# Main.net
KiCad netlist of a schematic drawn in Altium Designer
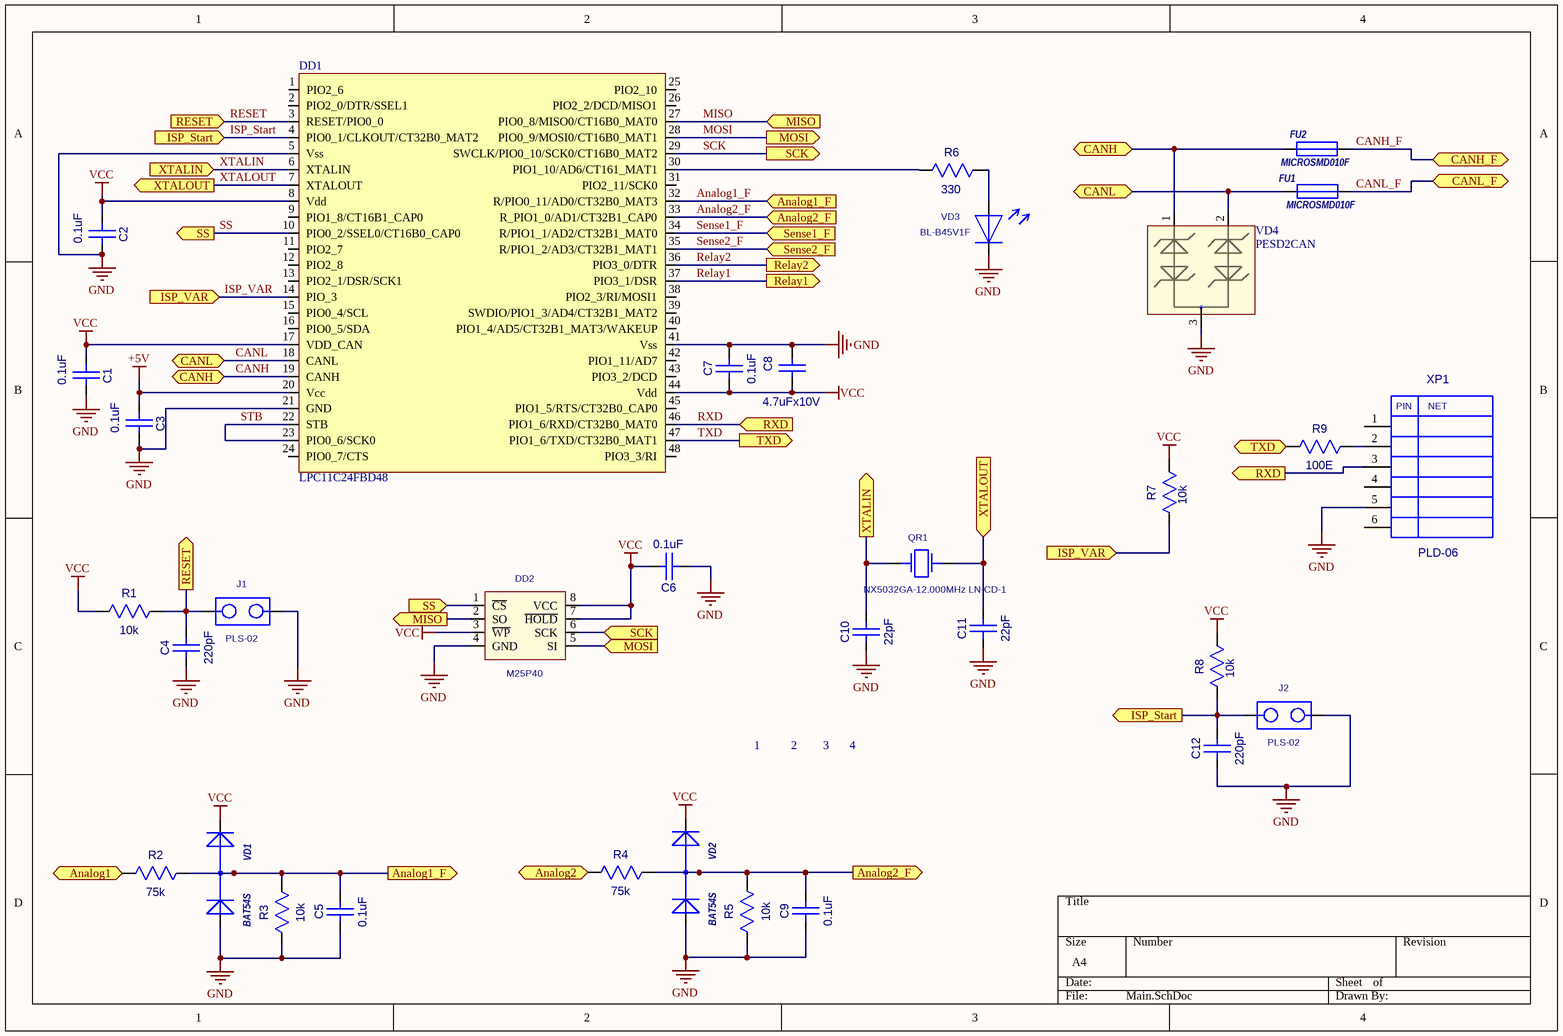
[diagram p0: Main.SchDoc]

(export (version "E")
  (design (tool "Eeschema 10.0.6"))
  (components
    (comp (ref "1")
      (value "REPER1.2")
      (footprint "REPER1.2")
      (libsource (lib "gprs_modem") (part "REPER1.2"))
    )
    (comp (ref "2")
      (value "REPER1.2")
      (footprint "REPER1.2")
      (libsource (lib "gprs_modem") (part "REPER1.2"))
    )
    (comp (ref "3")
      (value "REPER1.2")
      (footprint "REPER1.2")
      (libsource (lib "gprs_modem") (part "REPER1.2"))
    )
    (comp (ref "4")
      (value "REPER1.2")
      (footprint "REPER1.2")
      (libsource (lib "gprs_modem") (part "REPER1.2"))
    )
    (comp (ref "C1")
      (value "0.1uF")
      (footprint "CC0603-3M")
      (description "CC0603")
      (libsource (lib "gprs_modem") (part "CC0603"))
    )
    (comp (ref "C2")
      (value "0.1uF")
      (footprint "CC0603-3M")
      (description "CC0603")
      (libsource (lib "gprs_modem") (part "CC0603"))
    )
    (comp (ref "C3")
      (value "0.1uF")
      (footprint "CC0603-3M")
      (description "CC0603")
      (libsource (lib "gprs_modem") (part "CC0603"))
    )
    (comp (ref "C4")
      (value "220pF")
      (footprint "CC0603-3M")
      (description "CC0603")
      (libsource (lib "gprs_modem") (part "CC0603"))
    )
    (comp (ref "C5")
      (value "0.1uF")
      (footprint "CC0603-3M")
      (description "CC0603")
      (libsource (lib "gprs_modem") (part "CC0603"))
    )
    (comp (ref "C6")
      (value "0.1uF")
      (footprint "CC0603-3M")
      (description "CC0603")
      (libsource (lib "gprs_modem") (part "CC0603"))
    )
    (comp (ref "C7")
      (value "0.1uF")
      (footprint "CC0603-3M")
      (description "CC0603")
      (libsource (lib "gprs_modem") (part "CC0603"))
    )
    (comp (ref "C8")
      (value "4.7uFx10V")
      (footprint "CC0805-MIDI-2M1")
      (description "CC0805")
      (libsource (lib "gprs_modem") (part "CC0805"))
    )
    (comp (ref "C9")
      (value "0.1uF")
      (footprint "CC0603-3M")
      (description "CC0603")
      (libsource (lib "gprs_modem") (part "CC0603"))
    )
    (comp (ref "C10")
      (value "22pF")
      (footprint "CC0603-3M")
      (description "CC0603")
      (libsource (lib "gprs_modem") (part "CC0603"))
    )
    (comp (ref "C11")
      (value "22pF")
      (footprint "CC0603-3M")
      (description "CC0603")
      (libsource (lib "gprs_modem") (part "CC0603"))
    )
    (comp (ref "C12")
      (value "220pF")
      (footprint "CC0603-3M")
      (description "CC0603")
      (libsource (lib "gprs_modem") (part "CC0603"))
    )
    (comp (ref "DD1")
      (value "LPC11C24FBD48")
      (footprint "LQFP-48")
      (libsource (lib "gprs_modem_2") (part "LPC11C24FBD48"))
    )
    (comp (ref "DD2")
      (value "M25P40")
      (footprint "EIAJ_SO8")
      (description "S25FL016A0LMFI01")
      (libsource (lib "gprs_modem") (part "S25FL016A0LMFI01"))
    )
    (comp (ref "FU1")
      (value "MICROSMD010F")
      (footprint "RC1210")
      (description "MICROSMD")
      (libsource (lib "Schetchik") (part "MICROSMD"))
    )
    (comp (ref "FU2")
      (value "MICROSMD010F")
      (footprint "RC1210")
      (description "MICROSMD")
      (libsource (lib "Schetchik") (part "MICROSMD"))
    )
    (comp (ref "J1") (value "PLS-02") (footprint "PLS-02") (libsource (lib "gprs_modem") (part "PLS-02")))
    (comp (ref "J2") (value "PLS-02") (footprint "PLS-02") (libsource (lib "gprs_modem") (part "PLS-02")))
    (comp (ref "QR1")
      (value "NX5032GA-12.000MHz LN-CD-1")
      (footprint "AC5032_2")
      (description "AC5032/2")
      (libsource (lib "gprs_modem") (part "AC5032_2"))
    )
    (comp (ref "R1")
      (value "10k")
      (footprint "RC0603-3M")
      (description "RC0603")
      (libsource (lib "gprs_modem") (part "RC0603"))
    )
    (comp (ref "R2")
      (value "75k")
      (footprint "RC0603-3M")
      (description "RC0603")
      (libsource (lib "gprs_modem") (part "RC0603"))
    )
    (comp (ref "R3")
      (value "10k")
      (footprint "RC0603-3M")
      (description "RC0603")
      (libsource (lib "gprs_modem") (part "RC0603"))
    )
    (comp (ref "R4")
      (value "75k")
      (footprint "RC0603-3M")
      (description "RC0603")
      (libsource (lib "gprs_modem") (part "RC0603"))
    )
    (comp (ref "R5")
      (value "10k")
      (footprint "RC0603-3M")
      (description "RC0603")
      (libsource (lib "gprs_modem") (part "RC0603"))
    )
    (comp (ref "R6")
      (value "330")
      (footprint "RC0603-3M")
      (description "RC0603")
      (libsource (lib "gprs_modem") (part "RC0603"))
    )
    (comp (ref "R7")
      (value "10k")
      (footprint "RC0603-3M")
      (description "RC0603")
      (libsource (lib "gprs_modem") (part "RC0603"))
    )
    (comp (ref "R8")
      (value "10k")
      (footprint "RC0603-3M")
      (description "RC0603")
      (libsource (lib "gprs_modem") (part "RC0603"))
    )
    (comp (ref "R9")
      (value "100E")
      (footprint "RC0603-3M")
      (description "RC0603")
      (libsource (lib "gprs_modem") (part "RC0603"))
    )
    (comp (ref "VD1")
      (value "BAT54S")
      (footprint "SOT-23(GSD)")
      (description "1.0 Ampere General Purpose Rectifier")
      (libsource (lib "gprs_modem") (part "BAT54S"))
    )
    (comp (ref "VD2")
      (value "BAT54S")
      (footprint "SOT-23(GSD)")
      (description "1.0 Ampere General Purpose Rectifier")
      (libsource (lib "gprs_modem") (part "BAT54S"))
    )
    (comp (ref "VD3")
      (value "BL-B45V1F")
      (footprint "LED3")
      (description "LED_3")
      (libsource (lib "gprs_modem") (part "LED_3"))
    )
    (comp (ref "VD4")
      (value "PESD2CAN")
      (footprint "SOT-23(123)")
      (description "TVS for CAN")
      (libsource (lib "gprs_modem") (part "PESD2CAN"))
    )
    (comp (ref "XP1")
      (value "PLD-06")
      (footprint "PIN6")
      (description "PLD06")
      (libsource (lib "gprs_modem") (part "PLD-06"))
    )
  )
  (nets
    (net (code "1") (name "+5V") (class "Default")
      (node (ref "C3") (pin "1") (pinfunction "A_1") (pintype "passive"))
      (node (ref "DD1") (pin "20") (pinfunction "Vcc_20") (pintype "passive"))
    )
    (net (code "2") (name "/Analog1") (class "Default")
      (node (ref "R2") (pin "1") (pinfunction "A_1") (pintype "passive"))
    )
    (net (code "3") (name "/Analog1_F") (class "Default")
      (node (ref "C5") (pin "2") (pinfunction "B_2") (pintype "passive"))
      (node (ref "DD1") (pin "32") (pinfunction "R/PIO0_11/AD0/CT32B0_MAT3_32") (pintype "passive"))
      (node (ref "R2") (pin "2") (pinfunction "B_2") (pintype "passive"))
      (node (ref "R3") (pin "2") (pinfunction "B_2") (pintype "passive"))
      (node (ref "VD1") (pin "3") (pinfunction "AK_3") (pintype "passive"))
    )
    (net (code "4") (name "/Analog2") (class "Default")
      (node (ref "R4") (pin "1") (pinfunction "A_1") (pintype "passive"))
    )
    (net (code "5") (name "/Analog2_F") (class "Default")
      (node (ref "C9") (pin "2") (pinfunction "B_2") (pintype "passive"))
      (node (ref "DD1") (pin "33") (pinfunction "R_PIO1_0/AD1/CT32B1_CAP0_33") (pintype "passive"))
      (node (ref "R4") (pin "2") (pinfunction "B_2") (pintype "passive"))
      (node (ref "R5") (pin "2") (pinfunction "B_2") (pintype "passive"))
      (node (ref "VD2") (pin "3") (pinfunction "AK_3") (pintype "passive"))
    )
    (net (code "6") (name "/CANH") (class "Default")
      (node (ref "DD1") (pin "19") (pinfunction "CANH_19") (pintype "passive"))
      (node (ref "FU2") (pin "1") (pintype "passive"))
      (node (ref "VD4") (pin "1") (pinfunction "1_1") (pintype "passive"))
    )
    (net (code "7") (name "/CANH_F") (class "Default") (node (ref "FU2") (pin "2") (pintype "passive")))
    (net (code "8") (name "/CANL") (class "Default")
      (node (ref "DD1") (pin "18") (pinfunction "CANL_18") (pintype "passive"))
      (node (ref "FU1") (pin "1") (pintype "passive"))
      (node (ref "VD4") (pin "2") (pinfunction "2_2") (pintype "passive"))
    )
    (net (code "9") (name "/CANL_F") (class "Default") (node (ref "FU1") (pin "2") (pintype "passive")))
    (net (code "10") (name "/ISP_Start") (class "Default")
      (node (ref "C12") (pin "2") (pinfunction "B_2") (pintype "passive"))
      (node (ref "DD1") (pin "4") (pinfunction "PIO0_1/CLKOUT/CT32B0_MAT2_4") (pintype "passive"))
      (node (ref "J2") (pin "1") (pintype "passive"))
      (node (ref "R8") (pin "1") (pinfunction "A_1") (pintype "passive"))
    )
    (net (code "11") (name "/ISP_VAR") (class "Default")
      (node (ref "DD1") (pin "14") (pinfunction "PIO_3_14") (pintype "passive"))
      (node (ref "R7") (pin "1") (pinfunction "A_1") (pintype "passive"))
    )
    (net (code "12") (name "/MISO") (class "Default")
      (node (ref "DD1") (pin "27") (pinfunction "PIO0_8/MISO0/CT16B0_MAT0_27") (pintype "passive"))
      (node (ref "DD2") (pin "2") (pinfunction "SO_2") (pintype "passive"))
    )
    (net (code "13") (name "/MOSI") (class "Default")
      (node (ref "DD1") (pin "28") (pinfunction "PIO0_9/MOSI0/CT16B0_MAT1_28") (pintype "passive"))
      (node (ref "DD2") (pin "5") (pinfunction "SI_5") (pintype "passive"))
    )
    (net (code "14") (name "/RESET") (class "Default")
      (node (ref "C4") (pin "2") (pinfunction "B_2") (pintype "passive"))
      (node (ref "DD1") (pin "3") (pinfunction "RESET/PIO0_0_3") (pintype "passive"))
      (node (ref "J1") (pin "1") (pintype "passive"))
      (node (ref "R1") (pin "2") (pinfunction "B_2") (pintype "passive"))
    )
    (net (code "15") (name "/RXD") (class "Default")
      (node (ref "DD1") (pin "46") (pinfunction "PIO1_6/RXD/CT32B0_MAT0_46") (pintype "passive"))
      (node (ref "XP1") (pin "3") (pinfunction "3_3") (pintype "passive"))
    )
    (net (code "16") (name "/Relay1") (class "Default")
      (node (ref "DD1") (pin "37") (pinfunction "PIO3_1/DSR_37") (pintype "passive"))
    )
    (net (code "17") (name "/Relay2") (class "Default")
      (node (ref "DD1") (pin "36") (pinfunction "PIO3_0/DTR_36") (pintype "passive"))
    )
    (net (code "18") (name "/SCK") (class "Default")
      (node (ref "DD1") (pin "29") (pinfunction "SWCLK/PIO0_10/SCK0/CT16B0_MAT2_29") (pintype "passive"))
      (node (ref "DD2") (pin "6") (pinfunction "SCK_6") (pintype "passive"))
    )
    (net (code "19") (name "/SS") (class "Default")
      (node (ref "DD1") (pin "10") (pinfunction "PIO0_2/SSEL0/CT16B0_CAP0_10") (pintype "passive"))
      (node (ref "DD2") (pin "1") (pinfunction "~{CS}_1") (pintype "passive"))
    )
    (net (code "20") (name "/STB") (class "Default")
      (node (ref "DD1") (pin "22") (pinfunction "STB_22") (pintype "passive"))
      (node (ref "DD1") (pin "23") (pinfunction "PIO0_6/SCK0_23") (pintype "passive"))
    )
    (net (code "21") (name "/Sense1_F") (class "Default")
      (node (ref "DD1") (pin "34") (pinfunction "R/PIO1_1/AD2/CT32B1_MAT0_34") (pintype "passive"))
    )
    (net (code "22") (name "/Sense2_F") (class "Default")
      (node (ref "DD1") (pin "35") (pinfunction "R/PIO1_2/AD3/CT32B1_MAT1_35") (pintype "passive"))
    )
    (net (code "23") (name "/TXD") (class "Default")
      (node (ref "DD1") (pin "47") (pinfunction "PIO1_6/TXD/CT32B0_MAT1_47") (pintype "passive"))
      (node (ref "R9") (pin "1") (pinfunction "A_1") (pintype "passive"))
    )
    (net (code "24") (name "/XTALIN") (class "Default")
      (node (ref "C10") (pin "2") (pinfunction "B_2") (pintype "passive"))
      (node (ref "DD1") (pin "6") (pinfunction "XTALIN_6") (pintype "passive"))
      (node (ref "QR1") (pin "1") (pintype "passive"))
    )
    (net (code "25") (name "/XTALOUT") (class "Default")
      (node (ref "C11") (pin "2") (pinfunction "B_2") (pintype "passive"))
      (node (ref "DD1") (pin "7") (pinfunction "XTALOUT_7") (pintype "passive"))
      (node (ref "QR1") (pin "2") (pintype "passive"))
    )
    (net (code "26") (name "GND") (class "Default")
      (node (ref "C1") (pin "2") (pinfunction "B_2") (pintype "passive"))
      (node (ref "C10") (pin "1") (pinfunction "A_1") (pintype "passive"))
      (node (ref "C11") (pin "1") (pinfunction "A_1") (pintype "passive"))
      (node (ref "C12") (pin "1") (pinfunction "A_1") (pintype "passive"))
      (node (ref "C2") (pin "2") (pinfunction "B_2") (pintype "passive"))
      (node (ref "C3") (pin "2") (pinfunction "B_2") (pintype "passive"))
      (node (ref "C4") (pin "1") (pinfunction "A_1") (pintype "passive"))
      (node (ref "C5") (pin "1") (pinfunction "A_1") (pintype "passive"))
      (node (ref "C6") (pin "1") (pinfunction "A_1") (pintype "passive"))
      (node (ref "C7") (pin "2") (pinfunction "B_2") (pintype "passive"))
      (node (ref "C8") (pin "2") (pinfunction "B_2") (pintype "passive"))
      (node (ref "C9") (pin "1") (pinfunction "A_1") (pintype "passive"))
      (node (ref "DD1") (pin "21") (pinfunction "GND_21") (pintype "passive"))
      (node (ref "DD1") (pin "41") (pinfunction "Vss_41") (pintype "passive"))
      (node (ref "DD1") (pin "5") (pinfunction "Vss_5") (pintype "passive"))
      (node (ref "DD2") (pin "4") (pinfunction "GND_4") (pintype "passive"))
      (node (ref "J1") (pin "2") (pintype "passive"))
      (node (ref "J2") (pin "2") (pintype "passive"))
      (node (ref "R3") (pin "1") (pinfunction "A_1") (pintype "passive"))
      (node (ref "R5") (pin "1") (pinfunction "A_1") (pintype "passive"))
      (node (ref "VD1") (pin "1") (pinfunction "A_1") (pintype "passive"))
      (node (ref "VD2") (pin "1") (pinfunction "A_1") (pintype "passive"))
      (node (ref "VD3") (pin "1") (pintype "passive"))
      (node (ref "VD4") (pin "3") (pinfunction "3_3") (pintype "passive"))
      (node (ref "XP1") (pin "5") (pinfunction "5_5") (pintype "passive"))
    )
    (net (code "27") (name "Net-(DD1-PIO1_10{slash}AD6{slash}CT161_MAT1)") (class "Default")
      (node (ref "DD1") (pin "30") (pinfunction "PIO1_10/AD6/CT161_MAT1_30") (pintype "passive"))
      (node (ref "R6") (pin "1") (pinfunction "A_1") (pintype "passive"))
    )
    (net (code "28") (name "Net-(R6-B)") (class "Default")
      (node (ref "R6") (pin "2") (pinfunction "B_2") (pintype "passive"))
      (node (ref "VD3") (pin "2") (pintype "passive"))
    )
    (net (code "29") (name "Net-(R9-B)") (class "Default")
      (node (ref "R9") (pin "2") (pinfunction "B_2") (pintype "passive"))
      (node (ref "XP1") (pin "2") (pinfunction "2_2") (pintype "passive"))
    )
    (net (code "30") (name "VCC") (class "Default")
      (node (ref "C1") (pin "1") (pinfunction "A_1") (pintype "passive"))
      (node (ref "C2") (pin "1") (pinfunction "A_1") (pintype "passive"))
      (node (ref "C6") (pin "2") (pinfunction "B_2") (pintype "passive"))
      (node (ref "C7") (pin "1") (pinfunction "A_1") (pintype "passive"))
      (node (ref "C8") (pin "1") (pinfunction "A_1") (pintype "passive"))
      (node (ref "DD1") (pin "17") (pinfunction "VDD_CAN_17") (pintype "passive"))
      (node (ref "DD1") (pin "44") (pinfunction "Vdd_44") (pintype "passive"))
      (node (ref "DD1") (pin "8") (pinfunction "Vdd_8") (pintype "passive"))
      (node (ref "DD2") (pin "3") (pinfunction "~{WP}_3") (pintype "passive"))
      (node (ref "DD2") (pin "7") (pinfunction "~{HOLD}_7") (pintype "passive"))
      (node (ref "DD2") (pin "8") (pinfunction "VCC_8") (pintype "passive"))
      (node (ref "R1") (pin "1") (pinfunction "A_1") (pintype "passive"))
      (node (ref "R7") (pin "2") (pinfunction "B_2") (pintype "passive"))
      (node (ref "R8") (pin "2") (pinfunction "B_2") (pintype "passive"))
      (node (ref "VD1") (pin "2") (pinfunction "K_2") (pintype "passive"))
      (node (ref "VD2") (pin "2") (pinfunction "K_2") (pintype "passive"))
    )
    (net (code "31") (name "unconnected-(1-Pad1)") (class "Default")
      (node (ref "1") (pin "1") (pintype "passive"))
    )
    (net (code "32") (name "unconnected-(2-Pad1)") (class "Default")
      (node (ref "2") (pin "1") (pintype "passive"))
    )
    (net (code "33") (name "unconnected-(3-Pad1)") (class "Default")
      (node (ref "3") (pin "1") (pintype "passive"))
    )
    (net (code "34") (name "unconnected-(4-Pad1)") (class "Default")
      (node (ref "4") (pin "1") (pintype "passive"))
    )
    (net (code "35") (name "unconnected-(DD1-PIO0_4{slash}SCL-Pad15)") (class "Default")
      (node (ref "DD1") (pin "15") (pinfunction "PIO0_4/SCL_15") (pintype "passive"))
    )
    (net (code "36") (name "unconnected-(DD1-PIO0_5{slash}SDA-Pad16)") (class "Default")
      (node (ref "DD1") (pin "16") (pinfunction "PIO0_5/SDA_16") (pintype "passive"))
    )
    (net (code "37") (name "unconnected-(DD1-PIO0_7{slash}CTS-Pad24)") (class "Default")
      (node (ref "DD1") (pin "24") (pinfunction "PIO0_7/CTS_24") (pintype "passive"))
    )
    (net (code "38") (name "unconnected-(DD1-PIO1_4{slash}AD5{slash}CT32B1_MAT3{slash}WAKEUP-Pad40)") (class "Default")
      (node (ref "DD1") (pin "40") (pinfunction "PIO1_4/AD5/CT32B1_MAT3/WAKEUP_40") (pintype "passive"))
    )
    (net (code "39") (name "unconnected-(DD1-PIO1_5{slash}RTS{slash}CT32B0_CAP0-Pad45)") (class "Default")
      (node (ref "DD1") (pin "45") (pinfunction "PIO1_5/RTS/CT32B0_CAP0_45") (pintype "passive"))
    )
    (net (code "40") (name "unconnected-(DD1-PIO1_8{slash}CT16B1_CAP0-Pad9)") (class "Default")
      (node (ref "DD1") (pin "9") (pinfunction "PIO1_8/CT16B1_CAP0_9") (pintype "passive"))
    )
    (net (code "41") (name "unconnected-(DD1-PIO1_11{slash}AD7-Pad42)") (class "Default")
      (node (ref "DD1") (pin "42") (pinfunction "PIO1_11/AD7_42") (pintype "passive"))
    )
    (net (code "42") (name "unconnected-(DD1-PIO2_0{slash}DTR{slash}SSEL1-Pad2)") (class "Default")
      (node (ref "DD1") (pin "2") (pinfunction "PIO2_0/DTR/SSEL1_2") (pintype "passive"))
    )
    (net (code "43") (name "unconnected-(DD1-PIO2_1{slash}DSR{slash}SCK1-Pad13)") (class "Default")
      (node (ref "DD1") (pin "13") (pinfunction "PIO2_1/DSR/SCK1_13") (pintype "passive"))
    )
    (net (code "44") (name "unconnected-(DD1-PIO2_2{slash}DCD{slash}MISO1-Pad26)") (class "Default")
      (node (ref "DD1") (pin "26") (pinfunction "PIO2_2/DCD/MISO1_26") (pintype "passive"))
    )
    (net (code "45") (name "unconnected-(DD1-PIO2_3{slash}RI{slash}MOSI1-Pad38)") (class "Default")
      (node (ref "DD1") (pin "38") (pinfunction "PIO2_3/RI/MOSI1_38") (pintype "passive"))
    )
    (net (code "46") (name "unconnected-(DD1-PIO2_6-Pad1)") (class "Default")
      (node (ref "DD1") (pin "1") (pinfunction "PIO2_6_1") (pintype "passive"))
    )
    (net (code "47") (name "unconnected-(DD1-PIO2_7-Pad11)") (class "Default")
      (node (ref "DD1") (pin "11") (pinfunction "PIO2_7_11") (pintype "passive"))
    )
    (net (code "48") (name "unconnected-(DD1-PIO2_8-Pad12)") (class "Default")
      (node (ref "DD1") (pin "12") (pinfunction "PIO2_8_12") (pintype "passive"))
    )
    (net (code "49") (name "unconnected-(DD1-PIO2_10-Pad25)") (class "Default")
      (node (ref "DD1") (pin "25") (pinfunction "PIO2_10_25") (pintype "passive"))
    )
    (net (code "50") (name "unconnected-(DD1-PIO2_11{slash}SCK0-Pad31)") (class "Default")
      (node (ref "DD1") (pin "31") (pinfunction "PIO2_11/SCK0_31") (pintype "passive"))
    )
    (net (code "51") (name "unconnected-(DD1-PIO3_2{slash}DCD-Pad43)") (class "Default")
      (node (ref "DD1") (pin "43") (pinfunction "PIO3_2/DCD_43") (pintype "passive"))
    )
    (net (code "52") (name "unconnected-(DD1-PIO3_3{slash}RI-Pad48)") (class "Default")
      (node (ref "DD1") (pin "48") (pinfunction "PIO3_3/RI_48") (pintype "passive"))
    )
    (net (code "53") (name "unconnected-(DD1-SWDIO{slash}PIO1_3{slash}AD4{slash}CT32B1_MAT2-Pad39)") (class "Default")
      (node (ref "DD1") (pin "39") (pinfunction "SWDIO/PIO1_3/AD4/CT32B1_MAT2_39") (pintype "passive"))
    )
    (net (code "54") (name "unconnected-(XP1-Pad1)") (class "Default")
      (node (ref "XP1") (pin "1") (pinfunction "1_1") (pintype "passive"))
    )
    (net (code "55") (name "unconnected-(XP1-Pad4)") (class "Default")
      (node (ref "XP1") (pin "4") (pinfunction "4_4") (pintype "passive"))
    )
    (net (code "56") (name "unconnected-(XP1-Pad6)") (class "Default")
      (node (ref "XP1") (pin "6") (pinfunction "6_6") (pintype "passive"))
    )
  )
)
